# Camera.net
KiCad netlist of a schematic drawn in Altium Designer
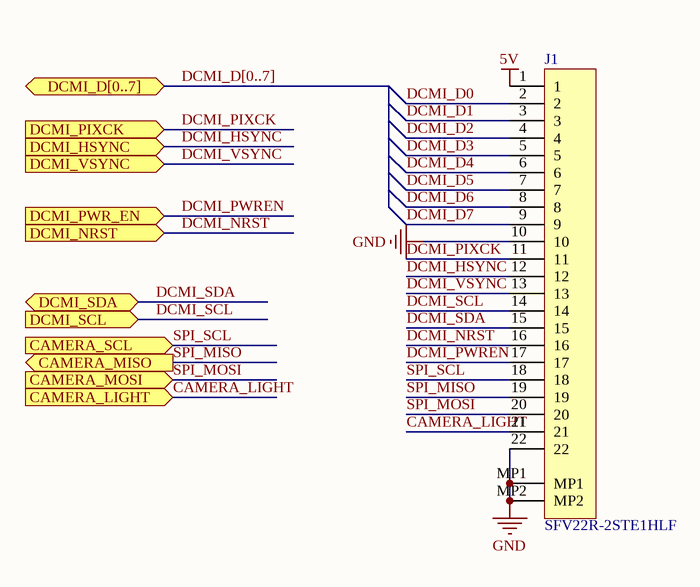
[diagram p0: Camera.SchDoc]

(export (version "E")
  (design (tool "Eeschema 10.0.6"))
  (components
    (comp (ref "J1")
      (value "SFV22R-2STE1HLF")
      (footprint "fpc-22")
      (description "Connector")
      (fields (field (name "MANUFACTURER") "Amphenol FCI"))
      (libsource (lib "yildizIoT Library") (part "FPC-22"))
    )
  )
  (nets
    (net (code "1") (name "/CAMERA_LIGHT") (class "Default")
      (node (ref "J1") (pin "21") (pinfunction "21_21") (pintype "passive"))
    )
    (net (code "2") (name "/DCMI_D0") (class "Default")
      (node (ref "J1") (pin "2") (pinfunction "2_2") (pintype "passive"))
    )
    (net (code "3") (name "/DCMI_D1") (class "Default")
      (node (ref "J1") (pin "3") (pinfunction "3_3") (pintype "passive"))
    )
    (net (code "4") (name "/DCMI_D2") (class "Default")
      (node (ref "J1") (pin "4") (pinfunction "4_4") (pintype "passive"))
    )
    (net (code "5") (name "/DCMI_D3") (class "Default")
      (node (ref "J1") (pin "5") (pinfunction "5_5") (pintype "passive"))
    )
    (net (code "6") (name "/DCMI_D4") (class "Default")
      (node (ref "J1") (pin "6") (pinfunction "6_6") (pintype "passive"))
    )
    (net (code "7") (name "/DCMI_D5") (class "Default")
      (node (ref "J1") (pin "7") (pinfunction "7_7") (pintype "passive"))
    )
    (net (code "8") (name "/DCMI_D6") (class "Default")
      (node (ref "J1") (pin "8") (pinfunction "8_8") (pintype "passive"))
    )
    (net (code "9") (name "/DCMI_D7") (class "Default")
      (node (ref "J1") (pin "9") (pinfunction "9_9") (pintype "passive"))
    )
    (net (code "11") (name "/DCMI_HSYNC") (class "Default")
      (node (ref "J1") (pin "12") (pinfunction "12_12") (pintype "passive"))
    )
    (net (code "12") (name "/DCMI_NRST") (class "Default")
      (node (ref "J1") (pin "16") (pinfunction "16_16") (pintype "passive"))
    )
    (net (code "13") (name "/DCMI_PIXCK") (class "Default")
      (node (ref "J1") (pin "11") (pinfunction "11_11") (pintype "passive"))
    )
    (net (code "14") (name "/DCMI_PWREN") (class "Default")
      (node (ref "J1") (pin "17") (pinfunction "17_17") (pintype "passive"))
    )
    (net (code "15") (name "/DCMI_SCL") (class "Default")
      (node (ref "J1") (pin "14") (pinfunction "14_14") (pintype "passive"))
    )
    (net (code "16") (name "/DCMI_SDA") (class "Default")
      (node (ref "J1") (pin "15") (pinfunction "15_15") (pintype "passive"))
    )
    (net (code "17") (name "/DCMI_VSYNC") (class "Default")
      (node (ref "J1") (pin "13") (pinfunction "13_13") (pintype "passive"))
    )
    (net (code "18") (name "/SPI_MISO") (class "Default")
      (node (ref "J1") (pin "19") (pinfunction "19_19") (pintype "passive"))
    )
    (net (code "19") (name "/SPI_MOSI") (class "Default")
      (node (ref "J1") (pin "20") (pinfunction "20_20") (pintype "passive"))
    )
    (net (code "20") (name "/SPI_SCL") (class "Default")
      (node (ref "J1") (pin "18") (pinfunction "18_18") (pintype "passive"))
    )
    (net (code "21") (name "5V") (class "Default")
      (node (ref "J1") (pin "1") (pinfunction "1_1") (pintype "passive"))
    )
    (net (code "22") (name "GND") (class "Default")
      (node (ref "J1") (pin "10") (pinfunction "10_10") (pintype "passive"))
      (node (ref "J1") (pin "22") (pinfunction "22_22") (pintype "passive"))
      (node (ref "J1") (pin "MP1") (pinfunction "MP1_MP1") (pintype "passive"))
      (node (ref "J1") (pin "MP2") (pinfunction "MP2_MP2") (pintype "passive"))
    )
  )
)
